# Ethernet.net
KiCad netlist of a schematic drawn in Altium Designer
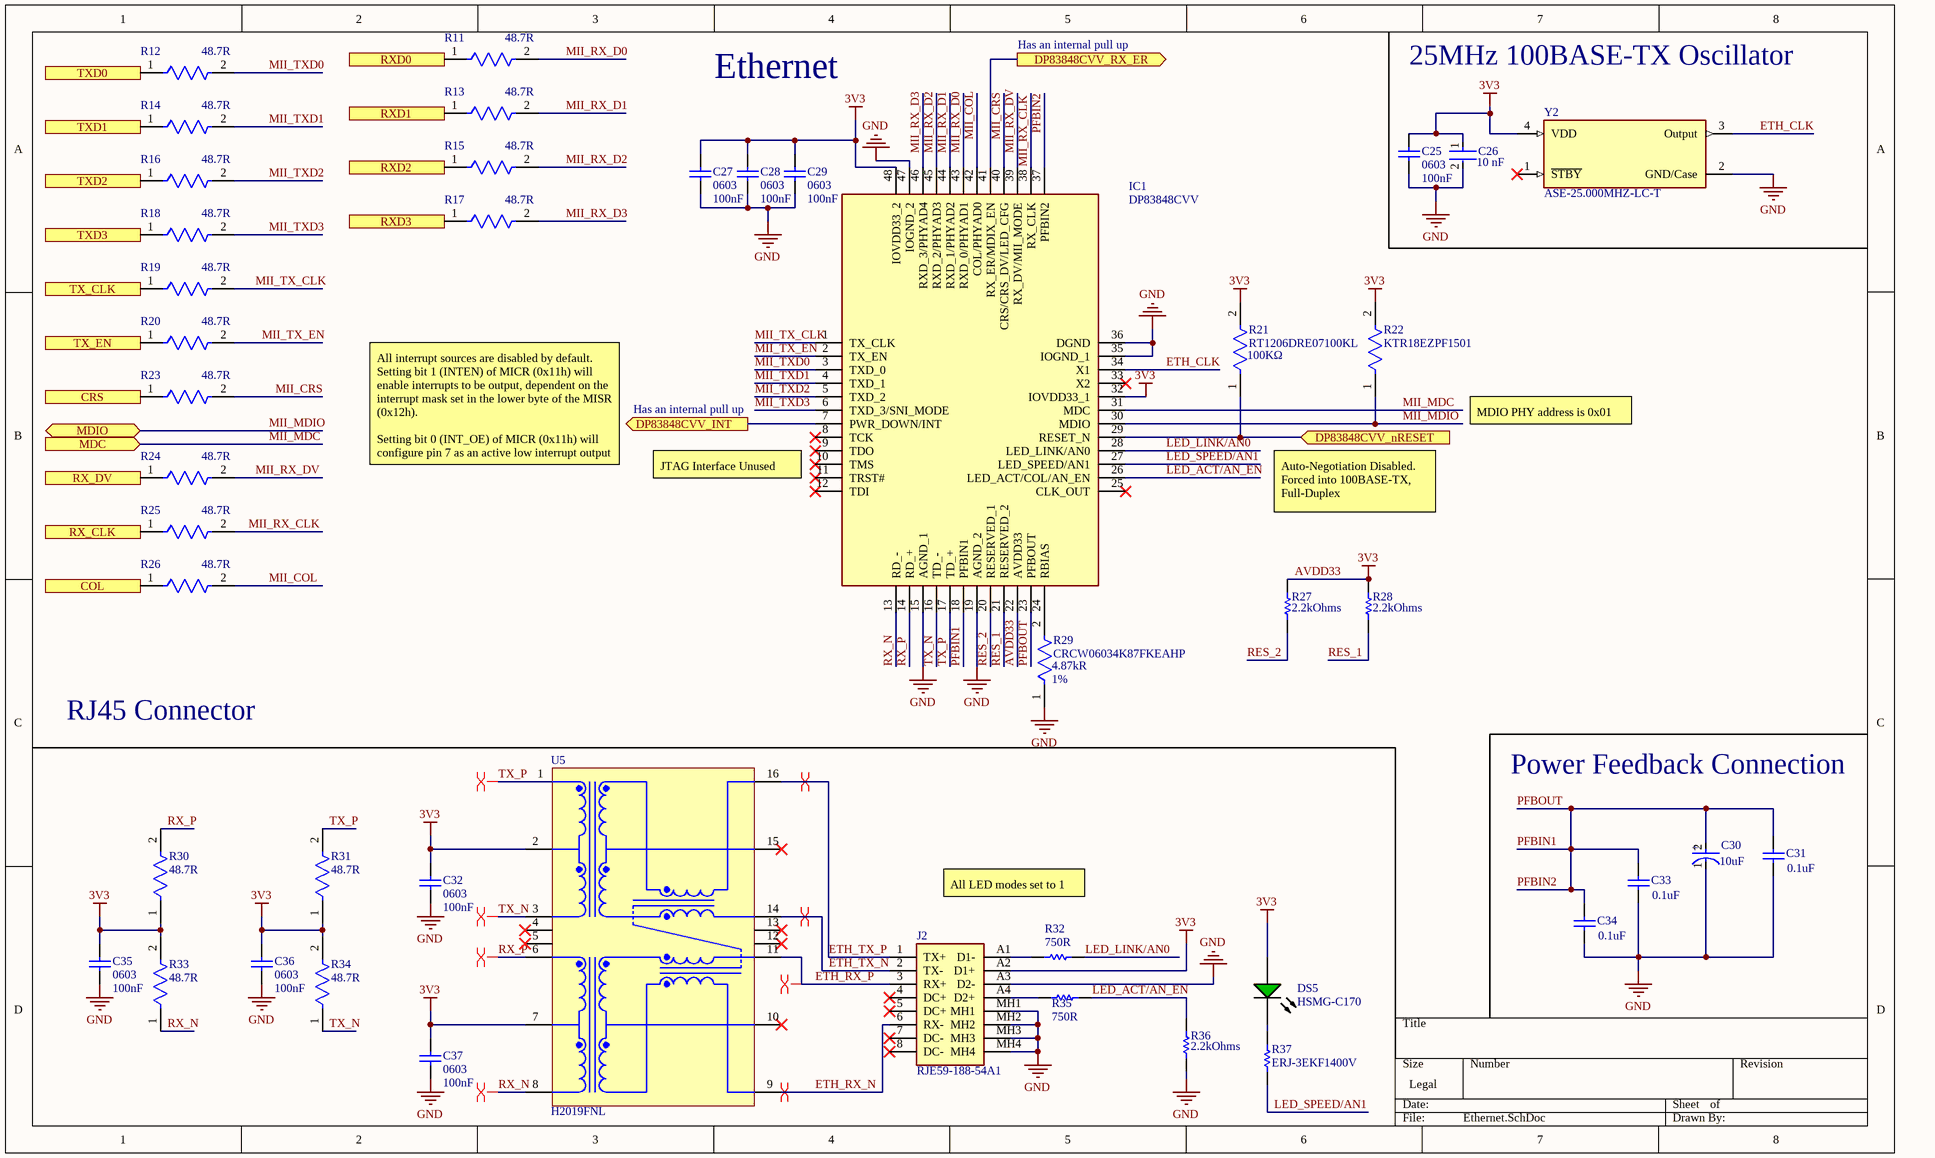
[diagram p0: Ethernet.SchDoc]

(export (version "E")
  (design (tool "Eeschema 10.0.6"))
  (components
    (comp (ref "C25")
      (value "C0603X104K5RACTU")
      (footprint "CAPC1608X87X35NL15T15")
      (fields
        (field (name "MANUFACTURER") "Kemet")
        (field (name "CASE CODE (IMPERIAL)") "0603")
        (field (name "CAPACITANCE") "100nF")
        (field (name "TOLERANCE") "10%")
        (field (name "VOLTAGE") "50V")
      )
      (libsource (lib "Altium Content Vault") (part "CAP"))
    )
    (comp (ref "C26")
      (value "10 nF")
      (footprint "FP-CC0603-DA-MFG")
      (description "CAP CER 10000PF 50V X7R 0603")
      (fields (field (name "TOLERANCE") "0.1") (field (name "MANUFACTURER PART NUMBER") "CC0603KRX7R9BB103"))
      (libsource (lib "Altium Content Vault") (part "11868f565c42a9108669ba33697ecf6"))
    )
    (comp (ref "C27")
      (value "C0603X104K5RACTU")
      (footprint "CAPC1608X87X35NL15T15")
      (fields
        (field (name "MANUFACTURER") "Kemet")
        (field (name "CASE CODE (IMPERIAL)") "0603")
        (field (name "CAPACITANCE") "100nF")
        (field (name "TOLERANCE") "10%")
        (field (name "VOLTAGE") "50V")
      )
      (libsource (lib "Altium Content Vault") (part "CAP"))
    )
    (comp (ref "C28")
      (value "C0603X104K5RACTU")
      (footprint "CAPC1608X87X35NL15T15")
      (fields
        (field (name "MANUFACTURER") "Kemet")
        (field (name "CASE CODE (IMPERIAL)") "0603")
        (field (name "CAPACITANCE") "100nF")
        (field (name "TOLERANCE") "10%")
        (field (name "VOLTAGE") "50V")
      )
      (libsource (lib "Altium Content Vault") (part "CAP"))
    )
    (comp (ref "C29")
      (value "C0603X104K5RACTU")
      (footprint "CAPC1608X87X35NL15T15")
      (fields
        (field (name "MANUFACTURER") "Kemet")
        (field (name "CASE CODE (IMPERIAL)") "0603")
        (field (name "CAPACITANCE") "100nF")
        (field (name "TOLERANCE") "10%")
        (field (name "VOLTAGE") "50V")
      )
      (libsource (lib "Altium Content Vault") (part "CAP"))
    )
    (comp (ref "C30")
      (value "T491B106K025AT")
      (footprint "FP-T491B106K025AT-MFG")
      (description "CAP TANT 10UF 10% 25V 1411")
      (fields
        (field (name "VOLTAGE") "25V")
        (field (name "TOLERANCE") "10%")
        (field (name "CAPACITANCE") "10uF")
      )
      (libsource (lib "Altium Content Vault") (part "a00bbbee19879c290e62620ae7e47b1"))
    )
    (comp (ref "C31")
      (value "0.1uF")
      (footprint "CAPC2113X120X50NL20T30")
      (fields
        (field (name "MANUFACTURER") "AVX Interconnect / Elco")
        (field (name "PART NUMBER") "TAJR104K020RNJ")
      )
      (libsource (lib "Altium Content Vault") (part "CAP"))
    )
    (comp (ref "C32")
      (value "C0603X104K5RACTU")
      (footprint "CAPC1608X87X35NL15T15")
      (fields
        (field (name "MANUFACTURER") "Kemet")
        (field (name "CASE CODE (IMPERIAL)") "0603")
        (field (name "CAPACITANCE") "100nF")
        (field (name "TOLERANCE") "10%")
        (field (name "VOLTAGE") "50V")
      )
      (libsource (lib "Altium Content Vault") (part "CAP"))
    )
    (comp (ref "C33")
      (value "0.1uF")
      (footprint "CAPC2113X120X50NL20T30")
      (fields
        (field (name "MANUFACTURER") "AVX Interconnect / Elco")
        (field (name "PART NUMBER") "TAJR104K020RNJ")
      )
      (libsource (lib "Altium Content Vault") (part "CAP"))
    )
    (comp (ref "C34")
      (value "0.1uF")
      (footprint "CAPC2113X120X50NL20T30")
      (fields
        (field (name "MANUFACTURER") "AVX Interconnect / Elco")
        (field (name "PART NUMBER") "TAJR104K020RNJ")
      )
      (libsource (lib "Altium Content Vault") (part "CAP"))
    )
    (comp (ref "C35")
      (value "C0603X104K5RACTU")
      (footprint "CAPC1608X87X35NL15T15")
      (fields
        (field (name "MANUFACTURER") "Kemet")
        (field (name "CASE CODE (IMPERIAL)") "0603")
        (field (name "CAPACITANCE") "100nF")
        (field (name "TOLERANCE") "10%")
        (field (name "VOLTAGE") "50V")
      )
      (libsource (lib "Altium Content Vault") (part "CAP"))
    )
    (comp (ref "C36")
      (value "C0603X104K5RACTU")
      (footprint "CAPC1608X87X35NL15T15")
      (fields
        (field (name "MANUFACTURER") "Kemet")
        (field (name "CASE CODE (IMPERIAL)") "0603")
        (field (name "CAPACITANCE") "100nF")
        (field (name "TOLERANCE") "10%")
        (field (name "VOLTAGE") "50V")
      )
      (libsource (lib "Altium Content Vault") (part "CAP"))
    )
    (comp (ref "C37")
      (value "C0603X104K5RACTU")
      (footprint "CAPC1608X87X35NL15T15")
      (fields
        (field (name "MANUFACTURER") "Kemet")
        (field (name "CASE CODE (IMPERIAL)") "0603")
        (field (name "CAPACITANCE") "100nF")
        (field (name "TOLERANCE") "10%")
        (field (name "VOLTAGE") "50V")
      )
      (libsource (lib "Altium Content Vault") (part "CAP"))
    )
    (comp (ref "DS5")
      (value "HSMG-C170")
      (footprint "AVAG-HSMX-C170_V")
      (description "Chip LED, Green, 2.2 V, -40 to 85 degC, 2-Pin SMD, Pb-Free, Tape and Reel")
      (fields (field (name "MANUFACTURER") "Avago"))
      (libsource (lib "Altium Content Vault") (part "LED_GREEN_A1K2-2"))
    )
    (comp (ref "IC1")
      (value "DP83848CVV")
      (footprint "SamacSys:QFP50P900X900X160-48N")
      (description "Integrated Circuit")
      (libsource (lib "*") (part "DP83848CVV"))
    )
    (comp (ref "J2")
      (value "RJE59-188-54A1")
      (footprint "SamacSys:RJE5918854A1")
      (description "Connector")
      (fields (field (name "MOUSER PART NUMBER") "523-RJE59-188-54A1"))
      (libsource (lib "*") (part "RJE59-188-54A1"))
    )
    (comp (ref "R11")
      (value "CRCW060348R7FKEA")
      (footprint "FP-CRCW0603-e3-IPC_C")
      (description "RES Thick Film, 48.7Ω, 1%, 0.1W, 100ppm/°C, 0603")
      (fields (field (name "TOLERANCE") "1%") (field (name "RESISTANCE") "48.7R"))
      (libsource (lib "Altium Content Vault") (part "1029c3af85768c4190bb7ad29bc67b5"))
    )
    (comp (ref "R12")
      (value "CRCW060348R7FKEA")
      (footprint "FP-CRCW0603-e3-IPC_C")
      (description "RES Thick Film, 48.7Ω, 1%, 0.1W, 100ppm/°C, 0603")
      (fields (field (name "TOLERANCE") "1%") (field (name "RESISTANCE") "48.7R"))
      (libsource (lib "Altium Content Vault") (part "1029c3af85768c4190bb7ad29bc67b5"))
    )
    (comp (ref "R13")
      (value "CRCW060348R7FKEA")
      (footprint "FP-CRCW0603-e3-IPC_C")
      (description "RES Thick Film, 48.7Ω, 1%, 0.1W, 100ppm/°C, 0603")
      (fields (field (name "TOLERANCE") "1%") (field (name "RESISTANCE") "48.7R"))
      (libsource (lib "Altium Content Vault") (part "1029c3af85768c4190bb7ad29bc67b5"))
    )
    (comp (ref "R14")
      (value "CRCW060348R7FKEA")
      (footprint "FP-CRCW0603-e3-IPC_C")
      (description "RES Thick Film, 48.7Ω, 1%, 0.1W, 100ppm/°C, 0603")
      (fields (field (name "TOLERANCE") "1%") (field (name "RESISTANCE") "48.7R"))
      (libsource (lib "Altium Content Vault") (part "1029c3af85768c4190bb7ad29bc67b5"))
    )
    (comp (ref "R15")
      (value "CRCW060348R7FKEA")
      (footprint "FP-CRCW0603-e3-IPC_C")
      (description "RES Thick Film, 48.7Ω, 1%, 0.1W, 100ppm/°C, 0603")
      (fields (field (name "TOLERANCE") "1%") (field (name "RESISTANCE") "48.7R"))
      (libsource (lib "Altium Content Vault") (part "1029c3af85768c4190bb7ad29bc67b5"))
    )
    (comp (ref "R16")
      (value "CRCW060348R7FKEA")
      (footprint "FP-CRCW0603-e3-IPC_C")
      (description "RES Thick Film, 48.7Ω, 1%, 0.1W, 100ppm/°C, 0603")
      (fields (field (name "TOLERANCE") "1%") (field (name "RESISTANCE") "48.7R"))
      (libsource (lib "Altium Content Vault") (part "1029c3af85768c4190bb7ad29bc67b5"))
    )
    (comp (ref "R17")
      (value "CRCW060348R7FKEA")
      (footprint "FP-CRCW0603-e3-IPC_C")
      (description "RES Thick Film, 48.7Ω, 1%, 0.1W, 100ppm/°C, 0603")
      (fields (field (name "TOLERANCE") "1%") (field (name "RESISTANCE") "48.7R"))
      (libsource (lib "Altium Content Vault") (part "1029c3af85768c4190bb7ad29bc67b5"))
    )
    (comp (ref "R18")
      (value "CRCW060348R7FKEA")
      (footprint "FP-CRCW0603-e3-IPC_C")
      (description "RES Thick Film, 48.7Ω, 1%, 0.1W, 100ppm/°C, 0603")
      (fields (field (name "TOLERANCE") "1%") (field (name "RESISTANCE") "48.7R"))
      (libsource (lib "Altium Content Vault") (part "1029c3af85768c4190bb7ad29bc67b5"))
    )
    (comp (ref "R19")
      (value "CRCW060348R7FKEA")
      (footprint "FP-CRCW0603-e3-IPC_C")
      (description "RES Thick Film, 48.7Ω, 1%, 0.1W, 100ppm/°C, 0603")
      (fields (field (name "TOLERANCE") "1%") (field (name "RESISTANCE") "48.7R"))
      (libsource (lib "Altium Content Vault") (part "1029c3af85768c4190bb7ad29bc67b5"))
    )
    (comp (ref "R20")
      (value "CRCW060348R7FKEA")
      (footprint "FP-CRCW0603-e3-IPC_C")
      (description "RES Thick Film, 48.7Ω, 1%, 0.1W, 100ppm/°C, 0603")
      (fields (field (name "TOLERANCE") "1%") (field (name "RESISTANCE") "48.7R"))
      (libsource (lib "Altium Content Vault") (part "1029c3af85768c4190bb7ad29bc67b5"))
    )
    (comp (ref "R21")
      (value "RT1206DRE07100KL")
      (footprint "FP-RT1206-MFG")
      (description "RES SMD 100K OHM 0.5% 1/4W 1206")
      (fields
        (field (name "MANUFACTURER") "Yageo")
        (field (name "OCTOPART") "https://octopart.com/rt1206dre07100kl-yageo-1189867")
        (field (name "RESISTANCE") "100KΩ")
      )
      (libsource (lib "Altium Content Vault") (part "1029c3af85768c4190bb7ad29bc67b5"))
    )
    (comp (ref "R22")
      (value "KTR18EZPF1501")
      (footprint "FP-KTR18-IPC_C")
      (description "Res Thick Film 1206 1.5kΩ 1% 0.1W ±100ppm/°C Automotive Paper T/R")
      (fields (field (name "TOLERANCE") "1%"))
      (libsource (lib "Altium Content Vault") (part "1029c3af85768c4190bb7ad29bc67b5"))
    )
    (comp (ref "R23")
      (value "CRCW060348R7FKEA")
      (footprint "FP-CRCW0603-e3-IPC_C")
      (description "RES Thick Film, 48.7Ω, 1%, 0.1W, 100ppm/°C, 0603")
      (fields (field (name "TOLERANCE") "1%") (field (name "RESISTANCE") "48.7R"))
      (libsource (lib "Altium Content Vault") (part "1029c3af85768c4190bb7ad29bc67b5"))
    )
    (comp (ref "R24")
      (value "CRCW060348R7FKEA")
      (footprint "FP-CRCW0603-e3-IPC_C")
      (description "RES Thick Film, 48.7Ω, 1%, 0.1W, 100ppm/°C, 0603")
      (fields (field (name "TOLERANCE") "1%") (field (name "RESISTANCE") "48.7R"))
      (libsource (lib "Altium Content Vault") (part "1029c3af85768c4190bb7ad29bc67b5"))
    )
    (comp (ref "R25")
      (value "CRCW060348R7FKEA")
      (footprint "FP-CRCW0603-e3-IPC_C")
      (description "RES Thick Film, 48.7Ω, 1%, 0.1W, 100ppm/°C, 0603")
      (fields (field (name "TOLERANCE") "1%") (field (name "RESISTANCE") "48.7R"))
      (libsource (lib "Altium Content Vault") (part "1029c3af85768c4190bb7ad29bc67b5"))
    )
    (comp (ref "R26")
      (value "CRCW060348R7FKEA")
      (footprint "FP-CRCW0603-e3-IPC_C")
      (description "RES Thick Film, 48.7Ω, 1%, 0.1W, 100ppm/°C, 0603")
      (fields (field (name "TOLERANCE") "1%") (field (name "RESISTANCE") "48.7R"))
      (libsource (lib "Altium Content Vault") (part "1029c3af85768c4190bb7ad29bc67b5"))
    )
    (comp (ref "R27")
      (value "RC0603FR-072K2L")
      (footprint "RESC1608X55X25LL10T15")
      (fields
        (field (name "TOLERANCE") "1%")
        (field (name "RESISTANCE") "2.2kOhms")
        (field (name "MANUFACTURER") "Yageo")
      )
      (libsource (lib "Altium Content Vault") (part "RES-2"))
    )
    (comp (ref "R28")
      (value "RC0603FR-072K2L")
      (footprint "RESC1608X55X25LL10T15")
      (fields
        (field (name "TOLERANCE") "1%")
        (field (name "RESISTANCE") "2.2kOhms")
        (field (name "MANUFACTURER") "Yageo")
      )
      (libsource (lib "Altium Content Vault") (part "RES-2"))
    )
    (comp (ref "R29")
      (value "CRCW06034K87FKEAHP")
      (footprint "FP-CRCW0603-HPe3-MFG")
      (description "RES Thick Film, 4.87kΩ, 1%, 0.33W, 100ppm/°C, 0603")
      (fields (field (name "TOLERANCE") "1%") (field (name "RESISTANCE") "4.87kR"))
      (libsource (lib "Altium Content Vault") (part "1029c3af85768c4190bb7ad29bc67b5"))
    )
    (comp (ref "R30")
      (value "CRCW060348R7FKEA")
      (footprint "FP-CRCW0603-e3-IPC_C")
      (description "RES Thick Film, 48.7Ω, 1%, 0.1W, 100ppm/°C, 0603")
      (fields (field (name "TOLERANCE") "1%") (field (name "RESISTANCE") "48.7R"))
      (libsource (lib "Altium Content Vault") (part "1029c3af85768c4190bb7ad29bc67b5"))
    )
    (comp (ref "R31")
      (value "CRCW060348R7FKEA")
      (footprint "FP-CRCW0603-e3-IPC_C")
      (description "RES Thick Film, 48.7Ω, 1%, 0.1W, 100ppm/°C, 0603")
      (fields (field (name "TOLERANCE") "1%") (field (name "RESISTANCE") "48.7R"))
      (libsource (lib "Altium Content Vault") (part "1029c3af85768c4190bb7ad29bc67b5"))
    )
    (comp (ref "R32")
      (value "CRCW0603750RJNEA")
      (footprint "RESC1609X50X30ML10T20")
      (fields (field (name "MANUFACTURER") "Vishay Dale") (field (name "RESISTANCE") "750R"))
      (libsource (lib "Altium Content Vault") (part "RES"))
    )
    (comp (ref "R33")
      (value "CRCW060348R7FKEA")
      (footprint "FP-CRCW0603-e3-IPC_C")
      (description "RES Thick Film, 48.7Ω, 1%, 0.1W, 100ppm/°C, 0603")
      (fields (field (name "TOLERANCE") "1%") (field (name "RESISTANCE") "48.7R"))
      (libsource (lib "Altium Content Vault") (part "1029c3af85768c4190bb7ad29bc67b5"))
    )
    (comp (ref "R34")
      (value "CRCW060348R7FKEA")
      (footprint "FP-CRCW0603-e3-IPC_C")
      (description "RES Thick Film, 48.7Ω, 1%, 0.1W, 100ppm/°C, 0603")
      (fields (field (name "TOLERANCE") "1%") (field (name "RESISTANCE") "48.7R"))
      (libsource (lib "Altium Content Vault") (part "1029c3af85768c4190bb7ad29bc67b5"))
    )
    (comp (ref "R35")
      (value "CRCW0603750RJNEA")
      (footprint "RESC1609X50X30ML10T20")
      (fields (field (name "MANUFACTURER") "Vishay Dale") (field (name "RESISTANCE") "750R"))
      (libsource (lib "Altium Content Vault") (part "RES"))
    )
    (comp (ref "R36")
      (value "RC0603FR-072K2L")
      (footprint "RESC1608X55X25LL10T15")
      (fields
        (field (name "TOLERANCE") "1%")
        (field (name "RESISTANCE") "2.2kOhms")
        (field (name "MANUFACTURER") "Yageo")
      )
      (libsource (lib "Altium Content Vault") (part "RES-2"))
    )
    (comp (ref "R37")
      (value "ERJ-3EKF1400V")
      (footprint "RESC1608X55X30NL15T15")
      (fields (field (name "MANUFACTURER") "Panasonic"))
      (libsource (lib "Altium Content Vault") (part "RES"))
    )
    (comp (ref "U5")
      (value "H2019FNL")
      (footprint "PULS-H2019FNL_V")
      (description "Telecom Transformer, 100BASE-TX, 0 to 70 degC, 16-Pin SMD, RoHS")
      (fields (field (name "MANUFACTURER") "Pulse Electronics"))
      (libsource (lib "Altium Content Vault") (part "PULS-H2019FNL-16"))
    )
    (comp (ref "Y2")
      (value "ASE-25.000MHZ-LC-T")
      (footprint "FP-ASE-MFG")
      (description "XTAL Oscillator 25MHz ±50ppm CMOS 3.3V 4-SMD 3.2mm x 2.5mm")
      (libsource (lib "Altium Content Vault") (part "61a724e6190563596ac712fef61ad37"))
    )
  )
  (nets
    (net (code "1") (name "/COL") (class "Default")
      (node (ref "R26") (pin "1") (pinfunction "1_1") (pintype "passive"))
    )
    (net (code "2") (name "/CRS") (class "Default")
      (node (ref "R23") (pin "1") (pinfunction "1_1") (pintype "passive"))
    )
    (net (code "3") (name "/DP83848CVV_INT") (class "Default")
      (node (ref "IC1") (pin "7") (pinfunction "PWR_DOWN/INT_7") (pintype "passive"))
    )
    (net (code "4") (name "/DP83848CVV_RX_ER") (class "Default")
      (node (ref "IC1") (pin "41") (pinfunction "RX_ER/MDIX_EN_41") (pintype "passive"))
    )
    (net (code "5") (name "/DP83848CVV_nRESET") (class "Default")
      (node (ref "IC1") (pin "29") (pinfunction "RESET_N_29") (pintype "passive"))
      (node (ref "R21") (pin "1") (pinfunction "1_1") (pintype "passive"))
    )
    (net (code "6") (name "/ETH_CLK") (class "Default")
      (node (ref "IC1") (pin "34") (pinfunction "X1_34") (pintype "passive"))
      (node (ref "Y2") (pin "3") (pinfunction "Output_3") (pintype "output"))
    )
    (net (code "7") (name "/ETH_RX_N") (class "Default")
      (node (ref "J2") (pin "6") (pinfunction "RX-_6") (pintype "passive"))
      (node (ref "U5") (pin "9") (pinfunction "RX-_9") (pintype "passive"))
    )
    (net (code "8") (name "/ETH_RX_P") (class "Default")
      (node (ref "J2") (pin "3") (pinfunction "RX+_3") (pintype "passive"))
      (node (ref "U5") (pin "11") (pinfunction "RX+_11") (pintype "passive"))
    )
    (net (code "9") (name "/ETH_TX_N") (class "Default")
      (node (ref "J2") (pin "2") (pinfunction "TX-_2") (pintype "passive"))
      (node (ref "U5") (pin "14") (pinfunction "TX-_14") (pintype "passive"))
    )
    (net (code "10") (name "/ETH_TX_P") (class "Default")
      (node (ref "J2") (pin "1") (pinfunction "TX+_1") (pintype "passive"))
      (node (ref "U5") (pin "16") (pinfunction "TX+_16") (pintype "passive"))
    )
    (net (code "11") (name "/LED_ACT{slash}AN_EN") (class "Default")
      (node (ref "IC1") (pin "26") (pinfunction "LED_ACT/COL/AN_EN_26") (pintype "passive"))
      (node (ref "R35") (pin "2") (pinfunction "2_2") (pintype "passive"))
      (node (ref "R36") (pin "2") (pinfunction "2_2") (pintype "passive"))
    )
    (net (code "12") (name "/LED_LINK{slash}AN0") (class "Default")
      (node (ref "IC1") (pin "28") (pinfunction "LED_LINK/AN0_28") (pintype "passive"))
      (node (ref "R32") (pin "2") (pinfunction "2_2") (pintype "passive"))
    )
    (net (code "13") (name "/LED_SPEED{slash}AN1") (class "Default")
      (node (ref "IC1") (pin "27") (pinfunction "LED_SPEED/AN1_27") (pintype "passive"))
      (node (ref "R37") (pin "1") (pinfunction "1_1") (pintype "passive"))
    )
    (net (code "14") (name "/MII_COL") (class "Default")
      (node (ref "IC1") (pin "42") (pinfunction "COL/PHYAD0_42") (pintype "passive"))
      (node (ref "R26") (pin "2") (pinfunction "2_2") (pintype "passive"))
    )
    (net (code "15") (name "/MII_CRS") (class "Default")
      (node (ref "IC1") (pin "40") (pinfunction "CRS/CRS_DV/LED_CFG_40") (pintype "passive"))
      (node (ref "R23") (pin "2") (pinfunction "2_2") (pintype "passive"))
    )
    (net (code "16") (name "/MII_MDC") (class "Default")
      (node (ref "IC1") (pin "31") (pinfunction "MDC_31") (pintype "passive"))
    )
    (net (code "17") (name "/MII_MDIO") (class "Default")
      (node (ref "IC1") (pin "30") (pinfunction "MDIO_30") (pintype "passive"))
      (node (ref "R22") (pin "1") (pinfunction "1_1") (pintype "passive"))
    )
    (net (code "18") (name "/MII_RX_CLK") (class "Default")
      (node (ref "IC1") (pin "38") (pinfunction "RX_CLK_38") (pintype "passive"))
      (node (ref "R25") (pin "2") (pinfunction "2_2") (pintype "passive"))
    )
    (net (code "19") (name "/MII_RX_D0") (class "Default")
      (node (ref "IC1") (pin "43") (pinfunction "RXD_0/PHYAD1_43") (pintype "passive"))
      (node (ref "R11") (pin "2") (pinfunction "2_2") (pintype "passive"))
    )
    (net (code "20") (name "/MII_RX_D1") (class "Default")
      (node (ref "IC1") (pin "44") (pinfunction "RXD_1/PHYAD2_44") (pintype "passive"))
      (node (ref "R13") (pin "2") (pinfunction "2_2") (pintype "passive"))
    )
    (net (code "21") (name "/MII_RX_D2") (class "Default")
      (node (ref "IC1") (pin "45") (pinfunction "RXD_2/PHYAD3_45") (pintype "passive"))
      (node (ref "R15") (pin "2") (pinfunction "2_2") (pintype "passive"))
    )
    (net (code "22") (name "/MII_RX_D3") (class "Default")
      (node (ref "IC1") (pin "46") (pinfunction "RXD_3/PHYAD4_46") (pintype "passive"))
      (node (ref "R17") (pin "2") (pinfunction "2_2") (pintype "passive"))
    )
    (net (code "23") (name "/MII_RX_DV") (class "Default")
      (node (ref "IC1") (pin "39") (pinfunction "RX_DV/MII_MODE_39") (pintype "passive"))
      (node (ref "R24") (pin "2") (pinfunction "2_2") (pintype "passive"))
    )
    (net (code "24") (name "/MII_TXD0") (class "Default")
      (node (ref "IC1") (pin "3") (pinfunction "TXD_0_3") (pintype "passive"))
      (node (ref "R12") (pin "2") (pinfunction "2_2") (pintype "passive"))
    )
    (net (code "25") (name "/MII_TXD1") (class "Default")
      (node (ref "IC1") (pin "4") (pinfunction "TXD_1_4") (pintype "passive"))
      (node (ref "R14") (pin "2") (pinfunction "2_2") (pintype "passive"))
    )
    (net (code "26") (name "/MII_TXD2") (class "Default")
      (node (ref "IC1") (pin "5") (pinfunction "TXD_2_5") (pintype "passive"))
      (node (ref "R16") (pin "2") (pinfunction "2_2") (pintype "passive"))
    )
    (net (code "27") (name "/MII_TXD3") (class "Default")
      (node (ref "IC1") (pin "6") (pinfunction "TXD_3/SNI_MODE_6") (pintype "passive"))
      (node (ref "R18") (pin "2") (pinfunction "2_2") (pintype "passive"))
    )
    (net (code "28") (name "/MII_TX_CLK") (class "Default")
      (node (ref "IC1") (pin "1") (pinfunction "TX_CLK_1") (pintype "passive"))
      (node (ref "R19") (pin "2") (pinfunction "2_2") (pintype "passive"))
    )
    (net (code "29") (name "/MII_TX_EN") (class "Default")
      (node (ref "IC1") (pin "2") (pinfunction "TX_EN_2") (pintype "passive"))
      (node (ref "R20") (pin "2") (pinfunction "2_2") (pintype "passive"))
    )
    (net (code "30") (name "/PFBIN1") (class "Default")
      (node (ref "C30") (pin "2") (pinfunction "A_2") (pintype "passive"))
      (node (ref "C31") (pin "2") (pinfunction "2_2") (pintype "passive"))
      (node (ref "C33") (pin "2") (pinfunction "2_2") (pintype "passive"))
      (node (ref "C34") (pin "2") (pinfunction "2_2") (pintype "passive"))
      (node (ref "IC1") (pin "18") (pinfunction "PFBIN1_18") (pintype "passive"))
      (node (ref "IC1") (pin "23") (pinfunction "PFBOUT_23") (pintype "passive"))
      (node (ref "IC1") (pin "37") (pinfunction "PFBIN2_37") (pintype "passive"))
    )
    (net (code "31") (name "/RES_1") (class "Default")
      (node (ref "IC1") (pin "21") (pinfunction "RESERVED_2_21") (pintype "passive"))
      (node (ref "R28") (pin "1") (pinfunction "1_1") (pintype "passive"))
    )
    (net (code "32") (name "/RES_2") (class "Default")
      (node (ref "IC1") (pin "20") (pinfunction "RESERVED_1_20") (pintype "passive"))
      (node (ref "R27") (pin "1") (pinfunction "1_1") (pintype "passive"))
    )
    (net (code "33") (name "/RXD0") (class "Default")
      (node (ref "R11") (pin "1") (pinfunction "1_1") (pintype "passive"))
    )
    (net (code "34") (name "/RXD1") (class "Default")
      (node (ref "R13") (pin "1") (pinfunction "1_1") (pintype "passive"))
    )
    (net (code "35") (name "/RXD2") (class "Default")
      (node (ref "R15") (pin "1") (pinfunction "1_1") (pintype "passive"))
    )
    (net (code "36") (name "/RXD3") (class "Default")
      (node (ref "R17") (pin "1") (pinfunction "1_1") (pintype "passive"))
    )
    (net (code "37") (name "/RX_CLK") (class "Default")
      (node (ref "R25") (pin "1") (pinfunction "1_1") (pintype "passive"))
    )
    (net (code "38") (name "/RX_DV") (class "Default")
      (node (ref "R24") (pin "1") (pinfunction "1_1") (pintype "passive"))
    )
    (net (code "39") (name "/RX_N") (class "Default")
      (node (ref "IC1") (pin "13") (pinfunction "RD_-_13") (pintype "passive"))
      (node (ref "R33") (pin "1") (pinfunction "1_1") (pintype "passive"))
      (node (ref "U5") (pin "8") (pinfunction "RD-_8") (pintype "passive"))
    )
    (net (code "40") (name "/RX_P") (class "Default")
      (node (ref "IC1") (pin "14") (pinfunction "RD_+_14") (pintype "passive"))
      (node (ref "R30") (pin "2") (pinfunction "2_2") (pintype "passive"))
      (node (ref "U5") (pin "6") (pinfunction "RD+_6") (pintype "passive"))
    )
    (net (code "41") (name "/TXD0") (class "Default")
      (node (ref "R12") (pin "1") (pinfunction "1_1") (pintype "passive"))
    )
    (net (code "42") (name "/TXD1") (class "Default")
      (node (ref "R14") (pin "1") (pinfunction "1_1") (pintype "passive"))
    )
    (net (code "43") (name "/TXD2") (class "Default")
      (node (ref "R16") (pin "1") (pinfunction "1_1") (pintype "passive"))
    )
    (net (code "44") (name "/TXD3") (class "Default")
      (node (ref "R18") (pin "1") (pinfunction "1_1") (pintype "passive"))
    )
    (net (code "45") (name "/TX_CLK") (class "Default")
      (node (ref "R19") (pin "1") (pinfunction "1_1") (pintype "passive"))
    )
    (net (code "46") (name "/TX_EN") (class "Default")
      (node (ref "R20") (pin "1") (pinfunction "1_1") (pintype "passive"))
    )
    (net (code "47") (name "/TX_N") (class "Default")
      (node (ref "IC1") (pin "16") (pinfunction "TD_-_16") (pintype "passive"))
      (node (ref "R34") (pin "1") (pinfunction "1_1") (pintype "passive"))
      (node (ref "U5") (pin "3") (pinfunction "TD-_3") (pintype "passive"))
    )
    (net (code "48") (name "/TX_P") (class "Default")
      (node (ref "IC1") (pin "17") (pinfunction "TD_+_17") (pintype "passive"))
      (node (ref "R31") (pin "2") (pinfunction "2_2") (pintype "passive"))
      (node (ref "U5") (pin "1") (pinfunction "TD+_1") (pintype "passive"))
    )
    (net (code "49") (name "3V3") (class "Default")
      (node (ref "C25") (pin "1") (pinfunction "1_1") (pintype "passive"))
      (node (ref "C26") (pin "1") (pinfunction "1_1") (pintype "passive"))
      (node (ref "C27") (pin "1") (pinfunction "1_1") (pintype "passive"))
      (node (ref "C28") (pin "1") (pinfunction "1_1") (pintype "passive"))
      (node (ref "C29") (pin "1") (pinfunction "1_1") (pintype "passive"))
      (node (ref "C32") (pin "1") (pinfunction "1_1") (pintype "passive"))
      (node (ref "C35") (pin "1") (pinfunction "1_1") (pintype "passive"))
      (node (ref "C36") (pin "1") (pinfunction "1_1") (pintype "passive"))
      (node (ref "C37") (pin "1") (pinfunction "1_1") (pintype "passive"))
      (node (ref "DS5") (pin "1") (pinfunction "A_1") (pintype "passive"))
      (node (ref "IC1") (pin "22") (pinfunction "AVDD33_22") (pintype "passive"))
      (node (ref "IC1") (pin "32") (pinfunction "IOVDD33_1_32") (pintype "passive"))
      (node (ref "IC1") (pin "48") (pinfunction "IOVDD33_2_48") (pintype "passive"))
      (node (ref "J2") (pin "A2") (pinfunction "D1+_A2") (pintype "passive"))
      (node (ref "R21") (pin "2") (pinfunction "2_2") (pintype "passive"))
      (node (ref "R22") (pin "2") (pinfunction "2_2") (pintype "passive"))
      (node (ref "R27") (pin "2") (pinfunction "2_2") (pintype "passive"))
      (node (ref "R28") (pin "2") (pinfunction "2_2") (pintype "passive"))
      (node (ref "R30") (pin "1") (pinfunction "1_1") (pintype "passive"))
      (node (ref "R31") (pin "1") (pinfunction "1_1") (pintype "passive"))
      (node (ref "R33") (pin "2") (pinfunction "2_2") (pintype "passive"))
      (node (ref "R34") (pin "2") (pinfunction "2_2") (pintype "passive"))
      (node (ref "U5") (pin "2") (pinfunction "TCT_2") (pintype "passive"))
      (node (ref "U5") (pin "7") (pinfunction "RCT_7") (pintype "passive"))
      (node (ref "Y2") (pin "4") (pinfunction "VDD_4") (pintype "input"))
    )
    (net (code "50") (name "GND") (class "Default")
      (node (ref "C25") (pin "2") (pinfunction "2_2") (pintype "passive"))
      (node (ref "C26") (pin "2") (pinfunction "2_2") (pintype "passive"))
      (node (ref "C27") (pin "2") (pinfunction "2_2") (pintype "passive"))
      (node (ref "C28") (pin "2") (pinfunction "2_2") (pintype "passive"))
      (node (ref "C29") (pin "2") (pinfunction "2_2") (pintype "passive"))
      (node (ref "C30") (pin "1") (pinfunction "C_1") (pintype "passive"))
      (node (ref "C31") (pin "1") (pinfunction "1_1") (pintype "passive"))
      (node (ref "C32") (pin "2") (pinfunction "2_2") (pintype "passive"))
      (node (ref "C33") (pin "1") (pinfunction "1_1") (pintype "passive"))
      (node (ref "C34") (pin "1") (pinfunction "1_1") (pintype "passive"))
      (node (ref "C35") (pin "2") (pinfunction "2_2") (pintype "passive"))
      (node (ref "C36") (pin "2") (pinfunction "2_2") (pintype "passive"))
      (node (ref "C37") (pin "2") (pinfunction "2_2") (pintype "passive"))
      (node (ref "IC1") (pin "15") (pinfunction "AGND_1_15") (pintype "passive"))
      (node (ref "IC1") (pin "19") (pinfunction "AGND_2_19") (pintype "passive"))
      (node (ref "IC1") (pin "35") (pinfunction "IOGND_1_35") (pintype "passive"))
      (node (ref "IC1") (pin "36") (pinfunction "DGND_36") (pintype "passive"))
      (node (ref "IC1") (pin "47") (pinfunction "IOGND_2_47") (pintype "passive"))
      (node (ref "J2") (pin "A3") (pinfunction "D2-_A3") (pintype "passive"))
      (node (ref "J2") (pin "MH1") (pinfunction "MH1_MH1") (pintype "passive"))
      (node (ref "J2") (pin "MH2") (pinfunction "MH2_MH2") (pintype "passive"))
      (node (ref "J2") (pin "MH3") (pinfunction "MH3_MH3") (pintype "passive"))
      (node (ref "J2") (pin "MH4") (pinfunction "MH4_MH4") (pintype "passive"))
      (node (ref "R29") (pin "1") (pinfunction "1_1") (pintype "passive"))
      (node (ref "R36") (pin "1") (pinfunction "1_1") (pintype "passive"))
      (node (ref "Y2") (pin "2") (pinfunction "GND/Case_2") (pintype "power_in"))
    )
    (net (code "51") (name "Net-(DS5-K)") (class "Default")
      (node (ref "DS5") (pin "2") (pinfunction "K_2") (pintype "passive"))
      (node (ref "R37") (pin "2") (pinfunction "2_2") (pintype "passive"))
    )
    (net (code "52") (name "Net-(IC1-RBIAS)") (class "Default")
      (node (ref "IC1") (pin "24") (pinfunction "RBIAS_24") (pintype "passive"))
      (node (ref "R29") (pin "2") (pinfunction "2_2") (pintype "passive"))
    )
    (net (code "53") (name "Net-(J2-D1-)") (class "Default")
      (node (ref "J2") (pin "A1") (pinfunction "D1-_A1") (pintype "passive"))
      (node (ref "R32") (pin "1") (pinfunction "1_1") (pintype "passive"))
    )
    (net (code "54") (name "Net-(J2-D2+)") (class "Default")
      (node (ref "J2") (pin "A4") (pinfunction "D2+_A4") (pintype "passive"))
      (node (ref "R35") (pin "1") (pinfunction "1_1") (pintype "passive"))
    )
    (net (code "55") (name "unconnected-(IC1-CLK_OUT-Pad25)") (class "Default")
      (node (ref "IC1") (pin "25") (pinfunction "CLK_OUT_25") (pintype "passive+no_connect"))
    )
    (net (code "56") (name "unconnected-(IC1-TCK-Pad8)") (class "Default")
      (node (ref "IC1") (pin "8") (pinfunction "TCK_8") (pintype "passive+no_connect"))
    )
    (net (code "57") (name "unconnected-(IC1-TDI-Pad12)") (class "Default")
      (node (ref "IC1") (pin "12") (pinfunction "TDI_12") (pintype "passive+no_connect"))
    )
    (net (code "58") (name "unconnected-(IC1-TDO-Pad9)") (class "Default")
      (node (ref "IC1") (pin "9") (pinfunction "TDO_9") (pintype "passive+no_connect"))
    )
    (net (code "59") (name "unconnected-(IC1-TMS-Pad10)") (class "Default")
      (node (ref "IC1") (pin "10") (pinfunction "TMS_10") (pintype "passive+no_connect"))
    )
    (net (code "60") (name "unconnected-(IC1-TRST#-Pad11)") (class "Default")
      (node (ref "IC1") (pin "11") (pinfunction "TRST#_11") (pintype "passive+no_connect"))
    )
    (net (code "61") (name "unconnected-(IC1-X2-Pad33)") (class "Default")
      (node (ref "IC1") (pin "33") (pinfunction "X2_33") (pintype "passive+no_connect"))
    )
    (net (code "62") (name "unconnected-(J2-DC+-Pad4)") (class "Default")
      (node (ref "J2") (pin "4") (pinfunction "DC+_4") (pintype "passive+no_connect"))
    )
    (net (code "63") (name "unconnected-(J2-DC+-Pad5)") (class "Default")
      (node (ref "J2") (pin "5") (pinfunction "DC+_5") (pintype "passive+no_connect"))
    )
    (net (code "64") (name "unconnected-(J2-DC--Pad7)") (class "Default")
      (node (ref "J2") (pin "7") (pinfunction "DC-_7") (pintype "passive+no_connect"))
    )
    (net (code "65") (name "unconnected-(J2-DC--Pad8)") (class "Default")
      (node (ref "J2") (pin "8") (pinfunction "DC-_8") (pintype "passive+no_connect"))
    )
    (net (code "66") (name "unconnected-(U5-NC-Pad4)") (class "Default")
      (node (ref "U5") (pin "4") (pinfunction "NC_4") (pintype "passive+no_connect"))
    )
    (net (code "67") (name "unconnected-(U5-NC-Pad5)") (class "Default")
      (node (ref "U5") (pin "5") (pinfunction "NC_5") (pintype "passive+no_connect"))
    )
    (net (code "68") (name "unconnected-(U5-NC-Pad12)") (class "Default")
      (node (ref "U5") (pin "12") (pinfunction "NC_12") (pintype "passive+no_connect"))
    )
    (net (code "69") (name "unconnected-(U5-NC-Pad13)") (class "Default")
      (node (ref "U5") (pin "13") (pinfunction "NC_13") (pintype "passive+no_connect"))
    )
    (net (code "70") (name "unconnected-(U5-RXCT-Pad10)") (class "Default")
      (node (ref "U5") (pin "10") (pinfunction "RXCT_10") (pintype "passive+no_connect"))
    )
    (net (code "71") (name "unconnected-(U5-TXCT-Pad15)") (class "Default")
      (node (ref "U5") (pin "15") (pinfunction "TXCT_15") (pintype "passive+no_connect"))
    )
    (net (code "72") (name "unconnected-(Y2-~{STBY}-Pad1)") (class "Default")
      (node (ref "Y2") (pin "1") (pinfunction "~{STBY}_1") (pintype "input+no_connect"))
    )
  )
)
